# SCK_DATA_BOARD_2_2.net
KiCad netlist of a schematic drawn in EAGLE
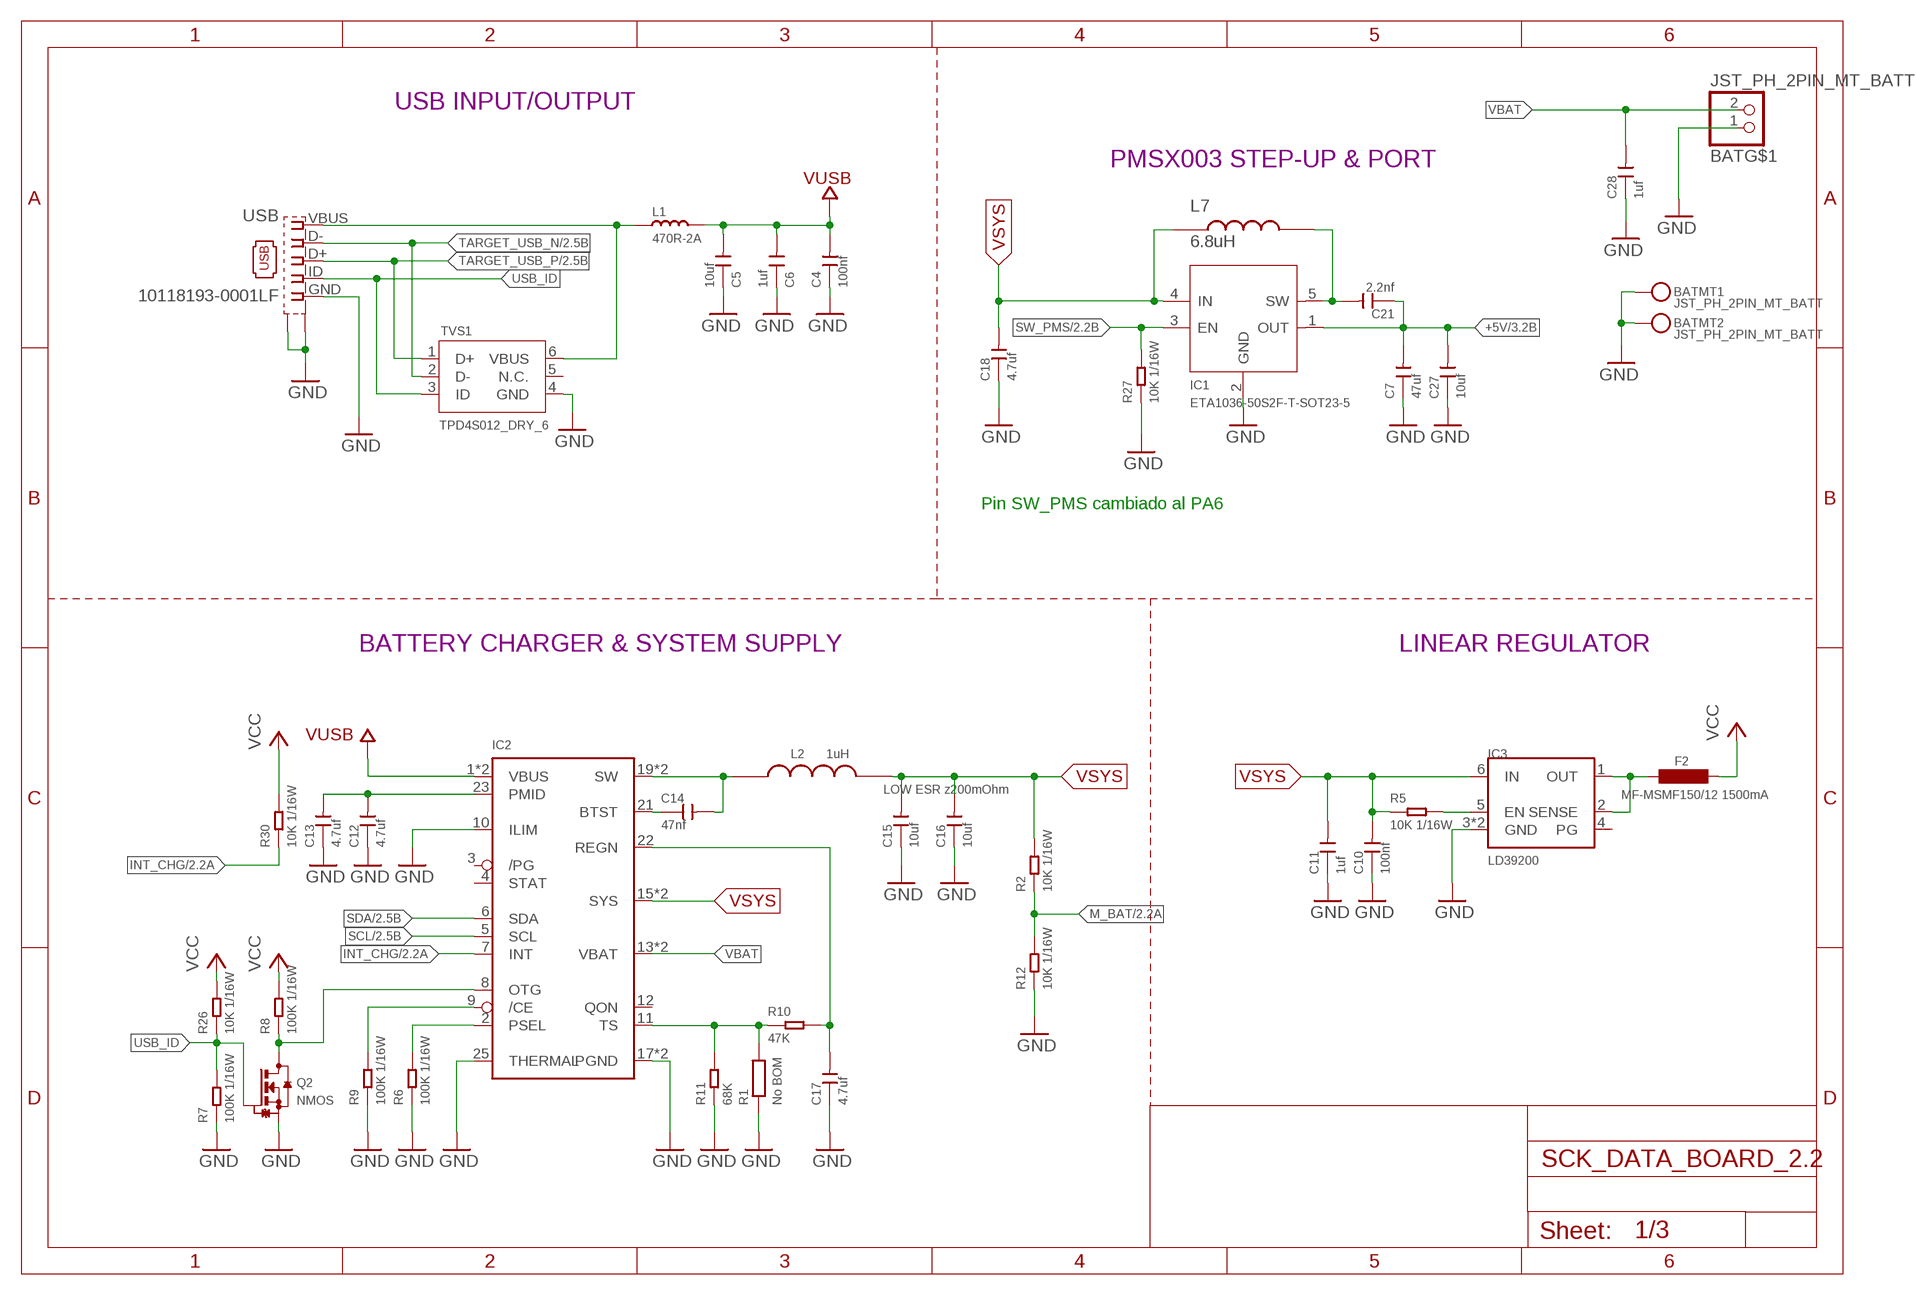
[diagram p0: schematic, sheet 1]
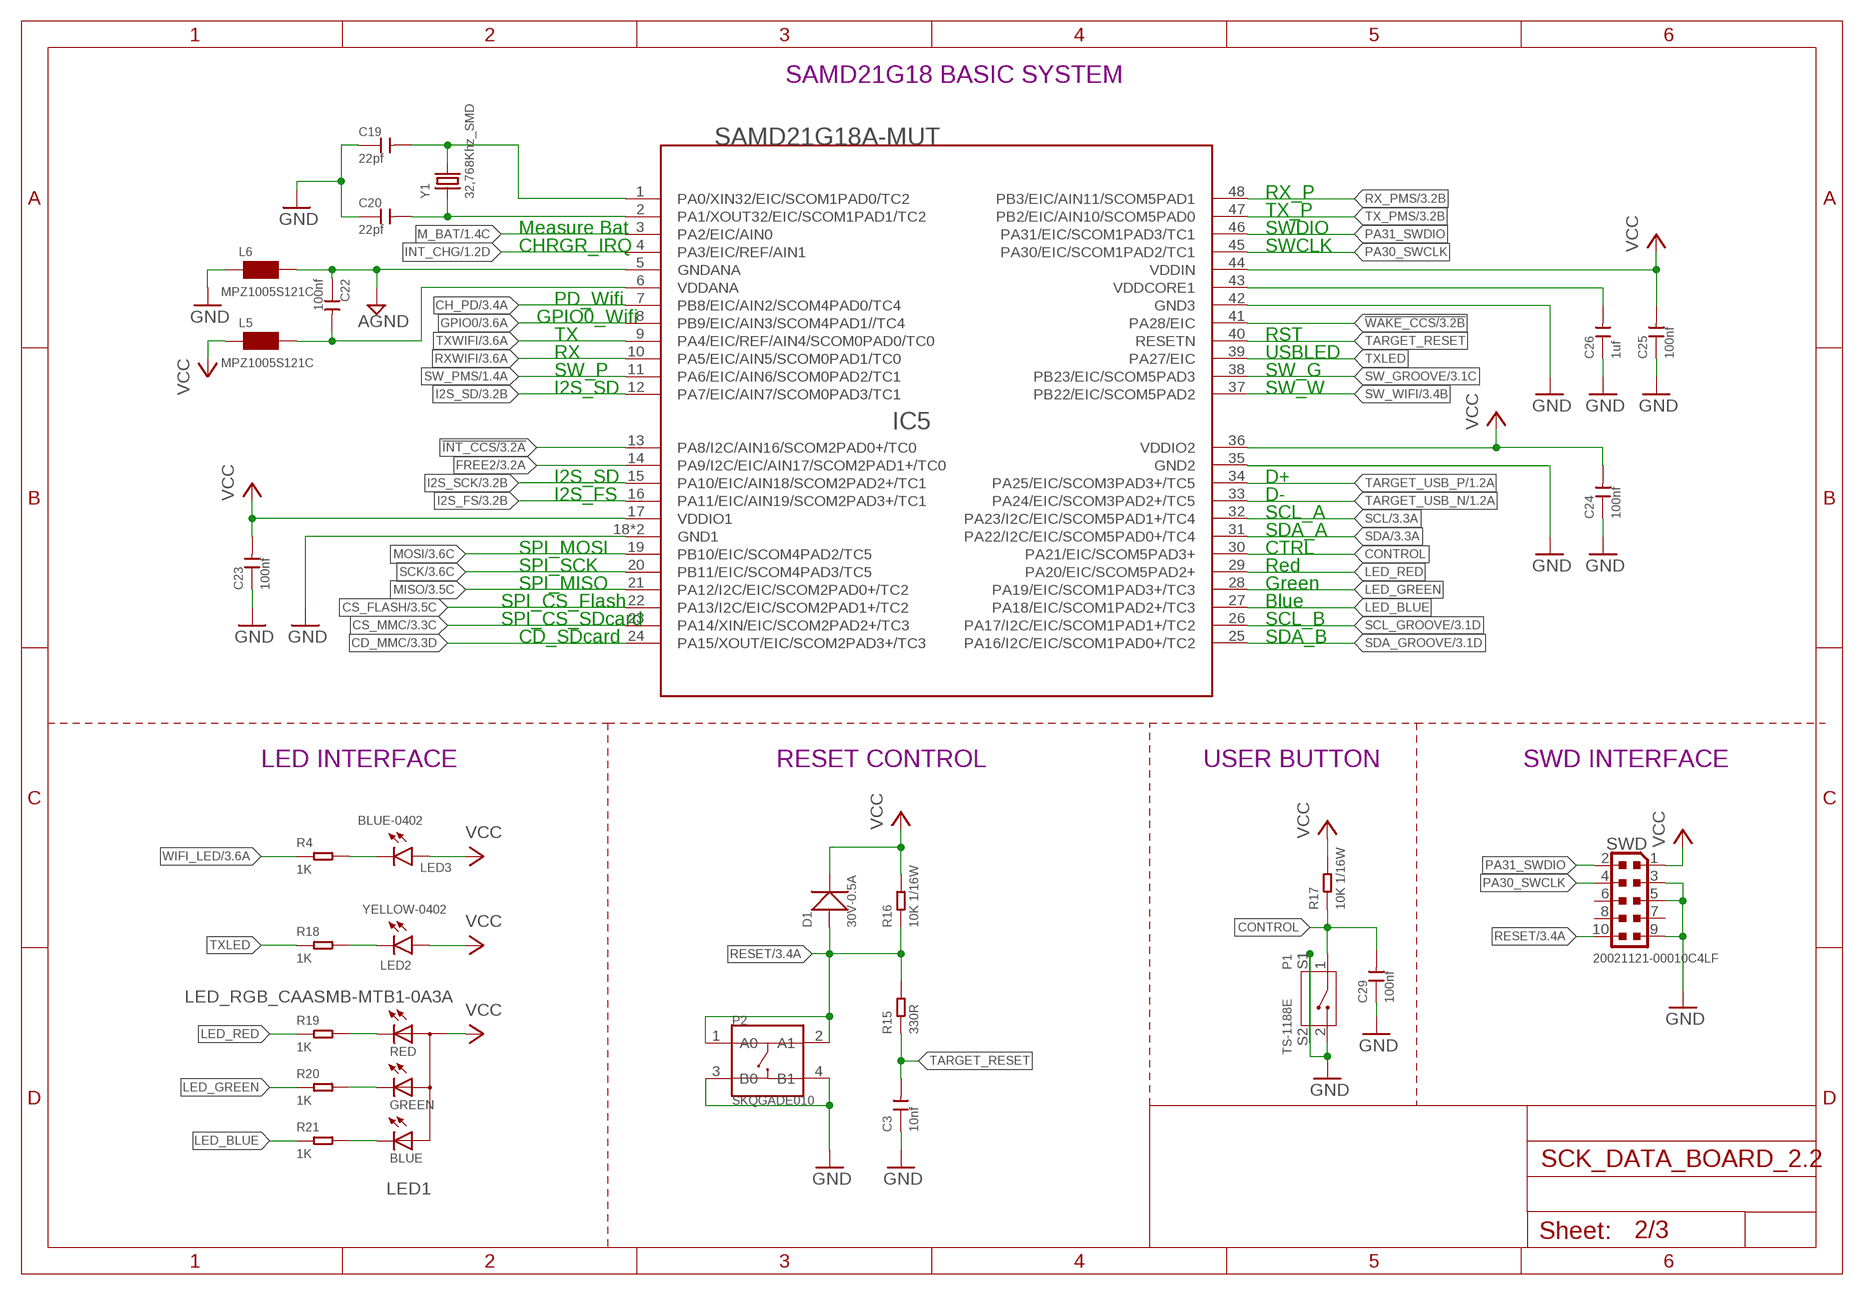
[diagram p1: schematic, sheet 2]
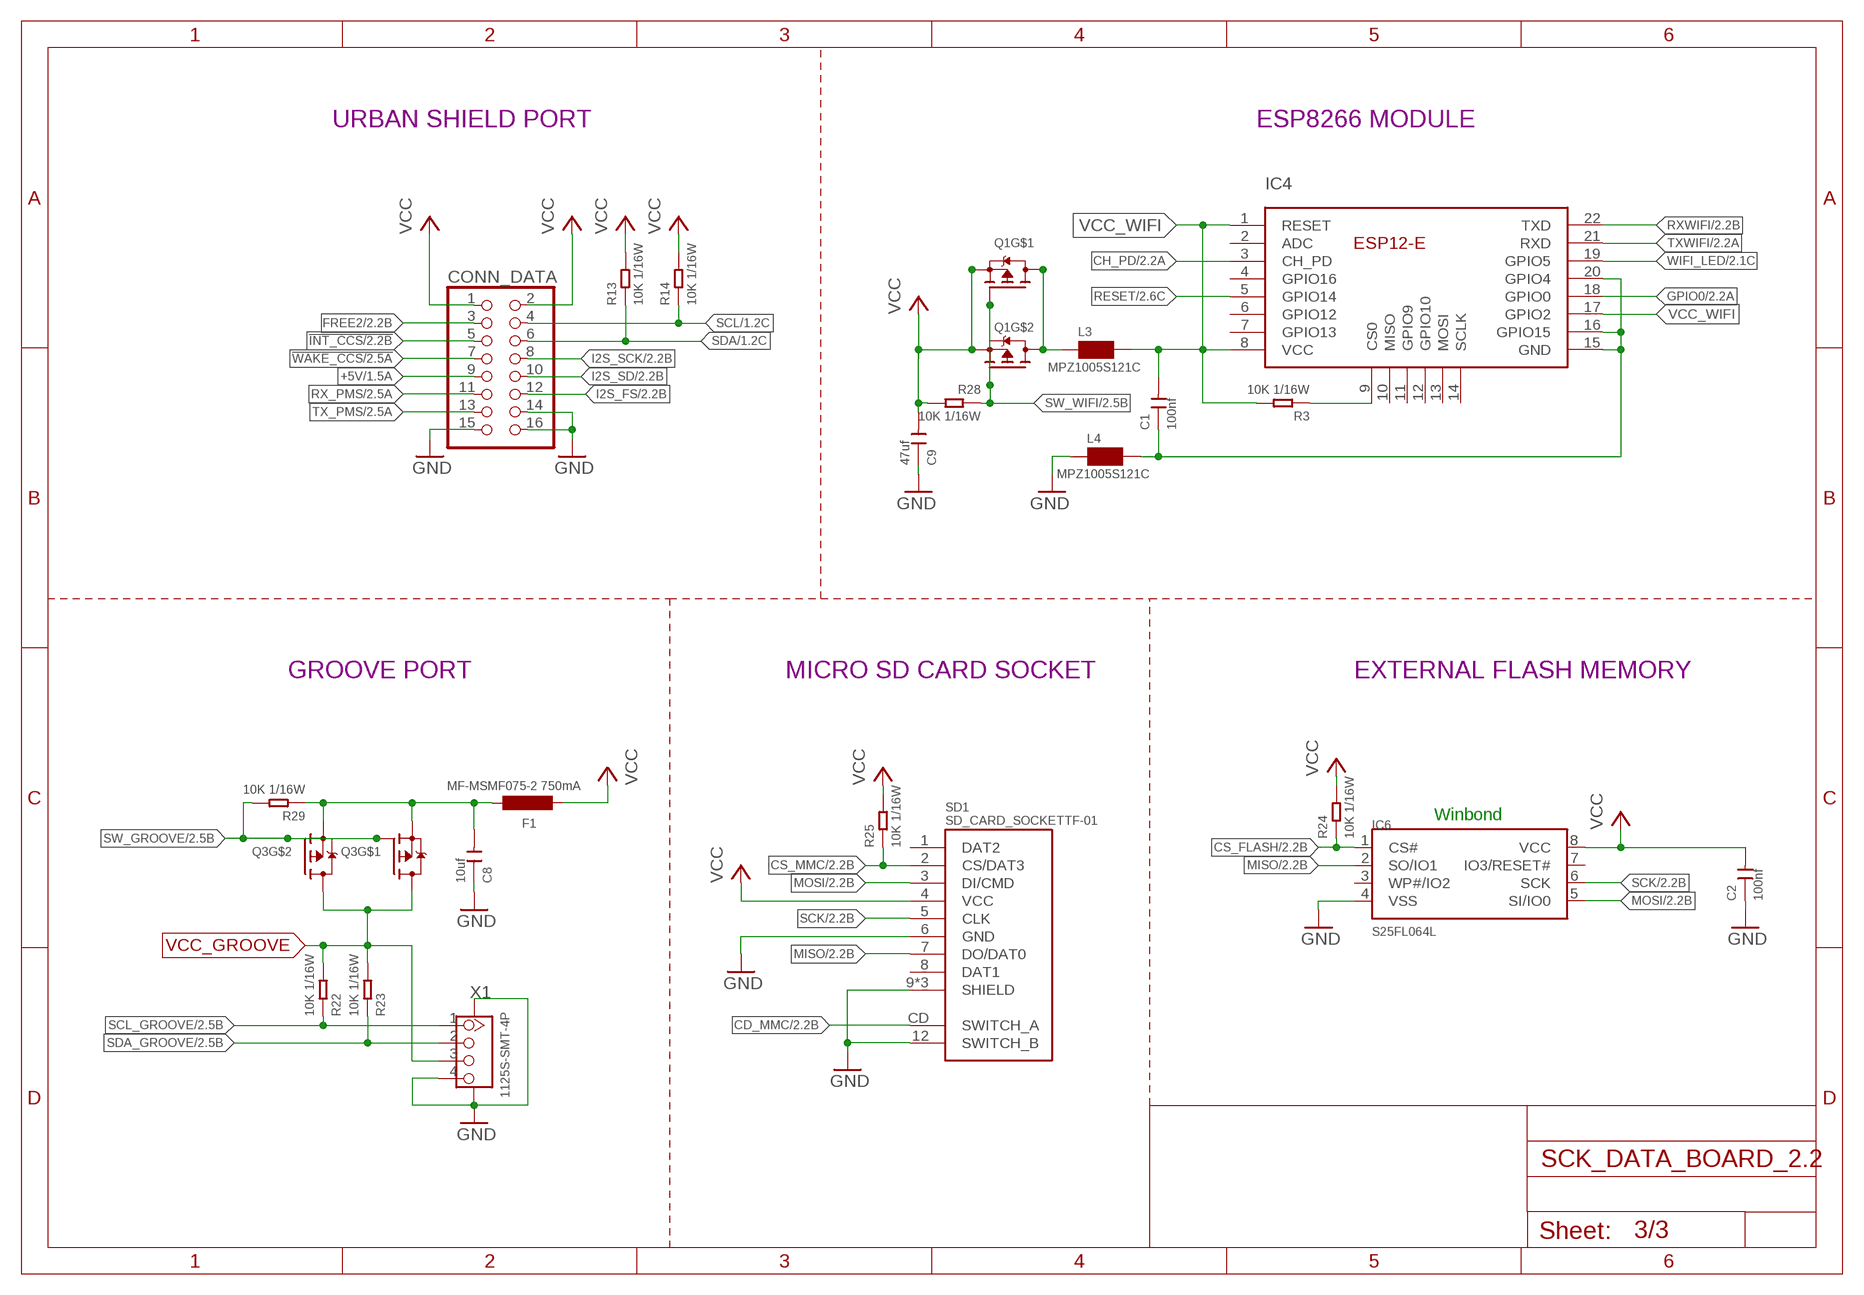
[diagram p2: schematic, sheet 3]

(export (version "E")
  (design (tool "Eeschema 10.0.6"))
  (components
    (comp (ref "C1")
      (value "100nf")
      (footprint "eagle-import:C0402")
      (fields (field (name "MPN") "CC0402KRX7R8BB104"))
      (libsource (lib "eagle-import") (part "CERAMIC-100NF-25V-10%-X7R(0402)"))
    )
    (comp (ref "C2")
      (value "100nf")
      (footprint "eagle-import:C0402")
      (fields (field (name "MPN") "CC0402KRX7R8BB104"))
      (libsource (lib "eagle-import") (part "CERAMIC-100NF-25V-10%-X7R(0402)"))
    )
    (comp (ref "C8")
      (value "10uf")
      (footprint "eagle-import:C1206")
      (fields (field (name "MPN") "CC1206KKX5R8BB106"))
      (libsource (lib "eagle-import") (part "CERAMIC-10UF-25V-10%-X5R(1206)"))
    )
    (comp (ref "C9")
      (value "47uf")
      (footprint "eagle-import:C1210")
      (fields (field (name "MPN") "GRM32ER71A476ME15L"))
      (libsource (lib "eagle-import") (part "CERAMIC-47UF-10V-20%-X7R(1210)"))
    )
    (comp (ref "CONN_DATA")
      (value "PINHD_2X8FEM_SMD")
      (footprint "eagle-import:PINHD_2X8_SMD_FEMALE_UNHOLED")
      (libsource (lib "eagle-import") (part "PINHD_2X8FEM_SMD"))
    )
    (comp (ref "F1")
      (value "MF-MSMF075-2 750mA")
      (footprint "eagle-import:L1812")
      (libsource (lib "eagle-import") (part "L-EUL1812"))
    )
    (comp (ref "IC4")
      (value "HANGAR_ESP-12-E")
      (footprint "eagle-import:HANGAR_ESP12-E")
      (libsource (lib "eagle-import") (part "HANGAR_ESP-12-E"))
    )
    (comp (ref "IC6")
      (value "S25FL064L")
      (footprint "eagle-import:SOIC_8-208MILS")
      (libsource (lib "eagle-import") (part "FLASH_S25FL064L"))
    )
    (comp (ref "L3")
      (value "MPZ1005S121C")
      (footprint "eagle-import:0402")
      (libsource (lib "eagle-import") (part "WE-CBF_0402"))
    )
    (comp (ref "L4")
      (value "MPZ1005S121C")
      (footprint "eagle-import:0402")
      (libsource (lib "eagle-import") (part "WE-CBF_0402"))
    )
    (comp (ref "Q1")
      (value "PMOS")
      (footprint "eagle-import:POWERPAK-SC70-6L")
      (fields (field (name "MPN") "SIA923AEDJ-T1-GE3 "))
      (libsource (lib "eagle-import") (part "MOSFET-PCHANNEL-DUAL"))
    )
    (comp (ref "Q3")
      (value "PMOS")
      (footprint "eagle-import:POWERPAK-SC70-6L")
      (libsource (lib "eagle-import") (part "MOSFET-PCHANNEL-DUAL"))
    )
    (comp (ref "R3")
      (value "10K 1/16W")
      (footprint "eagle-import:R0402")
      (fields (field (name "MPN") "RC0402FR-0710KL"))
      (libsource (lib "eagle-import") (part "SMD-RES-10K-1%-1/16W(0402)"))
    )
    (comp (ref "R13")
      (value "10K 1/16W")
      (footprint "eagle-import:R0402")
      (fields (field (name "MPN") "RC0402FR-0710KL"))
      (libsource (lib "eagle-import") (part "SMD-RES-10K-1%-1/16W(0402)"))
    )
    (comp (ref "R14")
      (value "10K 1/16W")
      (footprint "eagle-import:R0402")
      (fields (field (name "MPN") "RC0402FR-0710KL"))
      (libsource (lib "eagle-import") (part "SMD-RES-10K-1%-1/16W(0402)"))
    )
    (comp (ref "R22")
      (value "10K 1/16W")
      (footprint "eagle-import:R0402")
      (fields (field (name "MPN") "RC0402FR-0710KL"))
      (libsource (lib "eagle-import") (part "SMD-RES-10K-1%-1/16W(0402)"))
    )
    (comp (ref "R23")
      (value "10K 1/16W")
      (footprint "eagle-import:R0402")
      (fields (field (name "MPN") "RC0402FR-0710KL"))
      (libsource (lib "eagle-import") (part "SMD-RES-10K-1%-1/16W(0402)"))
    )
    (comp (ref "R24")
      (value "10K 1/16W")
      (footprint "eagle-import:R0402")
      (fields (field (name "MPN") "RC0402FR-0710KL"))
      (libsource (lib "eagle-import") (part "SMD-RES-10K-1%-1/16W(0402)"))
    )
    (comp (ref "R25")
      (value "10K 1/16W")
      (footprint "eagle-import:R0402")
      (fields (field (name "MPN") "RC0402FR-0710KL"))
      (libsource (lib "eagle-import") (part "SMD-RES-10K-1%-1/16W(0402)"))
    )
    (comp (ref "R28")
      (value "10K 1/16W")
      (footprint "eagle-import:R0402")
      (fields (field (name "MPN") "RC0402FR-0710KL"))
      (libsource (lib "eagle-import") (part "Seeed-Resistor_SMD-RES-10K-1%-1/16W(0402)"))
    )
    (comp (ref "R29")
      (value "10K 1/16W")
      (footprint "eagle-import:R0402")
      (fields (field (name "MPN") "RC0402FR-0710KL"))
      (libsource (lib "eagle-import") (part "Seeed-Resistor_SMD-RES-10K-1%-1/16W(0402)"))
    )
    (comp (ref "SD1")
      (value "SD_CARD_SOCKETTF-01")
      (footprint "eagle-import:TF-01")
      (fields (field (name "MPN") "320090008"))
      (libsource (lib "eagle-import") (part "SD_CARD_SOCKETTF-01"))
    )
    (comp (ref "X1")
      (value "1125S-SMT-4P")
      (footprint "eagle-import:CONNECTOR-NEW_HW4-SMD-2.0")
      (fields (field (name "MPN") "320110030"))
      (libsource (lib "eagle-import") (part "GROVE-CONNECTOR-SMDDD"))
    )
    (comp (ref "C3")
      (value "10nf")
      (footprint "eagle-import:C0402")
      (fields (field (name "MPN") "CC0402KRX7R9BB103"))
      (libsource (lib "eagle-import") (part "CERAMIC-10NF-50V-10%-X7R(0402)"))
    )
    (comp (ref "C19")
      (value "22pf")
      (footprint "eagle-import:C0402")
      (fields (field (name "MPN") "CC0402JRNPO9BN220"))
      (libsource (lib "eagle-import") (part "CERAMIC-22PF-50V-5%-NPO(0402)"))
    )
    (comp (ref "C20")
      (value "22pf")
      (footprint "eagle-import:C0402")
      (fields (field (name "MPN") "CC0402JRNPO9BN220"))
      (libsource (lib "eagle-import") (part "CERAMIC-22PF-50V-5%-NPO(0402)"))
    )
    (comp (ref "C22")
      (value "100nf")
      (footprint "eagle-import:C0402")
      (fields (field (name "MPN") "CC0402KRX7R8BB104"))
      (libsource (lib "eagle-import") (part "CERAMIC-100NF-25V-10%-X7R(0402)"))
    )
    (comp (ref "C23")
      (value "100nf")
      (footprint "eagle-import:C0402")
      (fields (field (name "MPN") "CC0402KRX7R8BB104"))
      (libsource (lib "eagle-import") (part "CERAMIC-100NF-25V-10%-X7R(0402)"))
    )
    (comp (ref "C24")
      (value "100nf")
      (footprint "eagle-import:C0402")
      (fields (field (name "MPN") "CC0402KRX7R8BB104"))
      (libsource (lib "eagle-import") (part "CERAMIC-100NF-25V-10%-X7R(0402)"))
    )
    (comp (ref "C25")
      (value "100nf")
      (footprint "eagle-import:C0402")
      (fields (field (name "MPN") "CC0402KRX7R8BB104"))
      (libsource (lib "eagle-import") (part "CERAMIC-100NF-25V-10%-X7R(0402)"))
    )
    (comp (ref "C26")
      (value "1uf")
      (footprint "eagle-import:C0805")
      (fields (field (name "MPN") "CC0805KKX7R8BB105"))
      (libsource (lib "eagle-import") (part "CERAMIC-1UF-25V-10%-X7R(0805)"))
    )
    (comp (ref "C29")
      (value "100nf")
      (footprint "eagle-import:C0402")
      (fields (field (name "MPN") "CC0402KRX7R8BB104"))
      (libsource (lib "eagle-import") (part "CERAMIC-100NF-25V-10%-X7R(0402)"))
    )
    (comp (ref "D1")
      (value "30V-0.5A")
      (footprint "eagle-import:SOD-323")
      (fields (field (name "MPN") "LRB551V-30T1G"))
      (libsource (lib "eagle-import") (part "SMD-DIODE-SCHOTTKY-30V-0.5A(SOD-323)"))
    )
    (comp (ref "IC5")
      (value "SAMD21G18A-MUT")
      (footprint "eagle-import:QFN48-7X7")
      (libsource (lib "eagle-import") (part "SAMD21G18A-MUT"))
    )
    (comp (ref "L5")
      (value "MPZ1005S121C")
      (footprint "eagle-import:0402")
      (libsource (lib "eagle-import") (part "WE-CBF_0402"))
    )
    (comp (ref "L6")
      (value "MPZ1005S121C")
      (footprint "eagle-import:0402")
      (libsource (lib "eagle-import") (part "WE-CBF_0402"))
    )
    (comp (ref "LED1")
      (value "LED_RGB_CAASMB-MTB1-0A3A")
      (footprint "eagle-import:HANGAR_P-LCC-4")
      (libsource (lib "eagle-import") (part "LED_RGB_CAASMB-MTB1-0A3A"))
    )
    (comp (ref "LED2")
      (value "YELLOW-0402")
      (footprint "eagle-import:CHIPLED_0402_YELLOW")
      (libsource (lib "eagle-import") (part "Hangar3D_37241589_LEDCHIPLED_0402_YELLOW"))
    )
    (comp (ref "LED3")
      (value "BLUE-0402")
      (footprint "eagle-import:CHIPLED_0402_BLUE")
      (libsource (lib "eagle-import") (part "LEDCHIPLED_0402_BLUE"))
    )
    (comp (ref "P1")
      (value "TS-1188E")
      (footprint "eagle-import:SW4-SMD-7.0X3.5X3.5MM-90D")
      (libsource (lib "eagle-import") (part "SMD-BUTTON(2+2P-7X3.5MM-90D)"))
    )
    (comp (ref "P2")
      (value "SKQGADE010")
      (footprint "eagle-import:SW4-SMD-5.2X5.2X1.5MM")
      (libsource (lib "eagle-import") (part "SMD-BUTTON(4P-5.2X5.2X1.5MM-SKQGADE010)-SKQGADE010"))
    )
    (comp (ref "R4")
      (value "1K")
      (footprint "eagle-import:R0402")
      (fields (field (name "MPN") "RC0402JR-071KL"))
      (libsource (lib "eagle-import") (part "SMD-RES-1K-5%-1/16W(0402)"))
    )
    (comp (ref "R15")
      (value "330R")
      (footprint "eagle-import:R0402")
      (fields (field (name "MPN") "RC0402FR-07330RL"))
      (libsource (lib "eagle-import") (part "SMD-RES-330R-1%-1/16W(0402)"))
    )
    (comp (ref "R16")
      (value "10K 1/16W")
      (footprint "eagle-import:R0402")
      (fields (field (name "MPN") "RC0402FR-0710KL"))
      (libsource (lib "eagle-import") (part "SMD-RES-10K-1%-1/16W(0402)"))
    )
    (comp (ref "R17")
      (value "10K 1/16W")
      (footprint "eagle-import:R0402")
      (fields (field (name "MPN") "RC0402FR-0710KL"))
      (libsource (lib "eagle-import") (part "SMD-RES-10K-1%-1/16W(0402)"))
    )
    (comp (ref "R18")
      (value "1K")
      (footprint "eagle-import:R0402")
      (fields (field (name "MPN") "RC0402JR-071KL"))
      (libsource (lib "eagle-import") (part "SMD-RES-1K-5%-1/16W(0402)"))
    )
    (comp (ref "R19")
      (value "1K")
      (footprint "eagle-import:R0402")
      (fields (field (name "MPN") "RC0402JR-071KL"))
      (libsource (lib "eagle-import") (part "SMD-RES-1K-5%-1/16W(0402)"))
    )
    (comp (ref "R20")
      (value "1K")
      (footprint "eagle-import:R0402")
      (fields (field (name "MPN") "RC0402JR-071KL"))
      (libsource (lib "eagle-import") (part "SMD-RES-1K-5%-1/16W(0402)"))
    )
    (comp (ref "R21")
      (value "1K")
      (footprint "eagle-import:R0402")
      (fields (field (name "MPN") "RC0402JR-071KL"))
      (libsource (lib "eagle-import") (part "SMD-RES-1K-5%-1/16W(0402)"))
    )
    (comp (ref "SWD")
      (value "20021121-00010C4LF")
      (footprint "eagle-import:2X05_SMD_1.27MM")
      (libsource (lib "eagle-import") (part "PINHEAD_PINHD-2X5SMD"))
    )
    (comp (ref "Y1")
      (value "32,768Khz_SMD")
      (footprint "eagle-import:CRISTALLI_RESONATOR_EPSON_FC_145")
      (fields (field (name "PART_NUMBER") "ABS07-32.768KHZ-T"))
      (libsource (lib "eagle-import") (part "CRISTALLI_0213_ABS07-32.768KHZ-T"))
    )
    (comp (ref "BAT")
      (value "JST_PH_2PIN_MT_BATT")
      (footprint "eagle-import:JSTPH2_BATT")
      (libsource (lib "eagle-import") (part "JST_PH_2PIN_MT_BATT"))
    )
    (comp (ref "C4")
      (value "100nf")
      (footprint "eagle-import:C0402")
      (fields (field (name "MPN") "CC0402KRX7R8BB104"))
      (libsource (lib "eagle-import") (part "CERAMIC-100NF-25V-10%-X7R(0402)"))
    )
    (comp (ref "C5")
      (value "10uf")
      (footprint "eagle-import:C1206")
      (fields (field (name "MPN") "CC1206KKX5R8BB106"))
      (libsource (lib "eagle-import") (part "CERAMIC-10UF-25V-10%-X5R(1206)"))
    )
    (comp (ref "C6")
      (value "1uf")
      (footprint "eagle-import:C0805")
      (fields (field (name "MPN") "CC0805KKX7R8BB105"))
      (libsource (lib "eagle-import") (part "CERAMIC-1UF-25V-10%-X7R(0805)"))
    )
    (comp (ref "C7")
      (value "47uf")
      (footprint "eagle-import:C0805")
      (fields (field (name "MPN") "CC0805MKX5R5BB476"))
      (libsource (lib "eagle-import") (part "CERAMIC-47UF-6.3V-20%-X5R(0805)"))
    )
    (comp (ref "C10")
      (value "100nf")
      (footprint "eagle-import:C0402")
      (fields (field (name "MPN") "CC0402KRX7R8BB104"))
      (libsource (lib "eagle-import") (part "CERAMIC-100NF-25V-10%-X7R(0402)"))
    )
    (comp (ref "C11")
      (value "1uf")
      (footprint "eagle-import:C0805")
      (fields (field (name "MPN") "CC0805KKX7R8BB105"))
      (libsource (lib "eagle-import") (part "CERAMIC-1UF-25V-10%-X7R(0805)"))
    )
    (comp (ref "C12")
      (value "4.7uf")
      (footprint "eagle-import:C0603")
      (fields (field (name "MPN") "CC0603KRX5R6BB475"))
      (libsource (lib "eagle-import") (part "CERAMIC-4.7UF-10V-10%-X5R(0603)"))
    )
    (comp (ref "C13")
      (value "4.7uf")
      (footprint "eagle-import:C0603")
      (fields (field (name "MPN") "CC0603KRX5R6BB475"))
      (libsource (lib "eagle-import") (part "CERAMIC-4.7UF-10V-10%-X5R(0603)"))
    )
    (comp (ref "C14")
      (value "47nf")
      (footprint "eagle-import:C0402")
      (fields (field (name "MPN") "CC0402KRX7R8BB473"))
      (libsource (lib "eagle-import") (part "CERAMIC-47NF-25V-10%-X7R(0402)"))
    )
    (comp (ref "C15")
      (value "10uf")
      (footprint "eagle-import:C0603")
      (fields (field (name "MPN") "CC0603KRX5R6BB106"))
      (libsource (lib "eagle-import") (part "Seeed-OPL-Capacitor_CERAMIC-10UF-10V-10%-X5R(0603)"))
    )
    (comp (ref "C16")
      (value "10uf")
      (footprint "eagle-import:C0603")
      (fields (field (name "MPN") "CC0603KRX5R6BB106"))
      (libsource (lib "eagle-import") (part "Seeed-OPL-Capacitor_CERAMIC-10UF-10V-10%-X5R(0603)"))
    )
    (comp (ref "C17")
      (value "4.7uf")
      (footprint "eagle-import:C0603")
      (fields (field (name "MPN") "CC0603KRX5R6BB475"))
      (libsource (lib "eagle-import") (part "CERAMIC-4.7UF-10V-10%-X5R(0603)"))
    )
    (comp (ref "C18")
      (value "4.7uf")
      (footprint "eagle-import:C0603")
      (fields (field (name "MPN") "CC0603KRX5R6BB475"))
      (libsource (lib "eagle-import") (part "CERAMIC-4.7UF-10V-10%-X5R(0603)"))
    )
    (comp (ref "C21")
      (value "2.2nf")
      (footprint "eagle-import:C0402")
      (fields (field (name "MPN") "CC0402KRX7R9BB222"))
      (libsource (lib "eagle-import") (part "CERAMIC-2.2NF-50V-10%-X7R(0402)"))
    )
    (comp (ref "C27")
      (value "10uf")
      (footprint "eagle-import:C0603")
      (fields (field (name "MPN") "CC0603KRX5R6BB106"))
      (libsource (lib "eagle-import") (part "CERAMIC-10UF-10V-10%-X5R(0603)"))
    )
    (comp (ref "C28")
      (value "1uf")
      (footprint "eagle-import:C0805")
      (fields (field (name "MPN") "CC0805KKX7R8BB105"))
      (libsource (lib "eagle-import") (part "CERAMIC-1UF-25V-10%-X7R(0805)"))
    )
    (comp (ref "F2")
      (value "MF-MSMF150/12 1500mA")
      (footprint "eagle-import:L1812")
      (libsource (lib "eagle-import") (part "L-EUL1812"))
    )
    (comp (ref "IC1")
      (value "ETA1036-50S2F-T-SOT23-5")
      (footprint "eagle-import:SOT-23-5")
      (fields (field (name "MPN") "ETA1036-50S2F-T"))
      (libsource (lib "eagle-import") (part "PMIC-ETA1036-50S2F-T(SOT23-5)"))
    )
    (comp (ref "IC2")
      (value "BQ24259_VQFN(24)")
      (footprint "eagle-import:24-PIN_VQFN_THPAD")
      (libsource (lib "eagle-import") (part "BQ24259_VQFN(24)"))
    )
    (comp (ref "IC3")
      (value "LD39200")
      (footprint "eagle-import:DFN6_3X3MM")
      (libsource (lib "eagle-import") (part "LD39200"))
    )
    (comp (ref "L1")
      (value "470R-2A")
      (footprint "eagle-import:L0805")
      (fields (field (name "MPN") "WLB2012-471T20"))
      (libsource (lib "eagle-import") (part "SMD-FERRITE-BEAD-470R-2A(0805)'0805'"))
    )
    (comp (ref "L2")
      (value "1uH")
      (footprint "eagle-import:HANGAR_C1210")
      (libsource (lib "eagle-import") (part "LQH32PN1R0NNCL"))
    )
    (comp (ref "L7")
      (value "6.8uH")
      (footprint "eagle-import:IND_BOURNS_SRN3015TA_3X3_SMD")
      (libsource (lib "eagle-import") (part "RCL_L_SMD_SRN3015TA-6R8M"))
    )
    (comp (ref "Q2")
      (value "NMOS")
      (footprint "eagle-import:NMOS_UMT3")
      (libsource (lib "eagle-import") (part "NMOS_RJU003N03FRAT106"))
    )
    (comp (ref "R1")
      (value "No BOM")
      (footprint "eagle-import:HANGAR_R0402")
      (libsource (lib "eagle-import") (part "HANGAR_R-EU_R0402"))
    )
    (comp (ref "R2")
      (value "10K 1/16W")
      (footprint "eagle-import:R0402")
      (fields (field (name "MPN") "RC0402FR-0710KL"))
      (libsource (lib "eagle-import") (part "SMD-RES-10K-1%-1/16W(0402)"))
    )
    (comp (ref "R5")
      (value "10K 1/16W")
      (footprint "eagle-import:R0402")
      (fields (field (name "MPN") "RC0402FR-0710KL"))
      (libsource (lib "eagle-import") (part "SMD-RES-10K-1%-1/16W(0402)"))
    )
    (comp (ref "R6")
      (value "100K 1/16W")
      (footprint "eagle-import:R0402")
      (fields (field (name "MPN") "RC0402JR-07100KL"))
      (libsource (lib "eagle-import") (part "SMD-RES-100K-5%-1/16W(0402)"))
    )
    (comp (ref "R7")
      (value "100K 1/16W")
      (footprint "eagle-import:R0402")
      (fields (field (name "MPN") "RC0402JR-07100KL"))
      (libsource (lib "eagle-import") (part "SMD-RES-100K-5%-1/16W(0402)"))
    )
    (comp (ref "R8")
      (value "100K 1/16W")
      (footprint "eagle-import:R0402")
      (fields (field (name "MPN") "RC0402JR-07100KL"))
      (libsource (lib "eagle-import") (part "SMD-RES-100K-5%-1/16W(0402)"))
    )
    (comp (ref "R9")
      (value "100K 1/16W")
      (footprint "eagle-import:R0402")
      (fields (field (name "MPN") "RC0402JR-07100KL"))
      (libsource (lib "eagle-import") (part "SMD-RES-100K-5%-1/16W(0402)"))
    )
    (comp (ref "R10")
      (value "47K")
      (footprint "eagle-import:R0402")
      (fields (field (name "MPN") "RC0402JR-0747KL"))
      (libsource (lib "eagle-import") (part "SMD-RES-47K-5%-1/16W(0402)"))
    )
    (comp (ref "R11")
      (value "68K")
      (footprint "eagle-import:R0402")
      (fields (field (name "MPN") "RC0402JR-0768KL"))
      (libsource (lib "eagle-import") (part "SMD-RES-68K-50V-5%(0402)"))
    )
    (comp (ref "R12")
      (value "10K 1/16W")
      (footprint "eagle-import:R0402")
      (fields (field (name "MPN") "RC0402FR-0710KL"))
      (libsource (lib "eagle-import") (part "SMD-RES-10K-1%-1/16W(0402)"))
    )
    (comp (ref "R26")
      (value "10K 1/16W")
      (footprint "eagle-import:R0402")
      (fields (field (name "MPN") "RC0402FR-0710KL"))
      (libsource (lib "eagle-import") (part "SMD-RES-10K-1%-1/16W(0402)"))
    )
    (comp (ref "R27")
      (value "10K 1/16W")
      (footprint "eagle-import:R0402")
      (fields (field (name "MPN") "RC0402FR-0710KL"))
      (libsource (lib "eagle-import") (part "Seeed-Resistor_SMD-RES-10K-1%-1/16W(0402)"))
    )
    (comp (ref "R30")
      (value "10K 1/16W")
      (footprint "eagle-import:R0402")
      (fields (field (name "MPN") "RC0402FR-0710KL"))
      (libsource (lib "eagle-import") (part "SMD-RES-10K-1%-1/16W(0402)"))
    )
    (comp (ref "TVS1")
      (value "TPD4S012_DRY_6")
      (footprint "eagle-import:DRY6")
      (libsource (lib "eagle-import") (part "TPD4S012_DRY_6"))
    )
    (comp (ref "USB")
      (value "10118193-0001LF")
      (footprint "eagle-import:CON2_USB_MICRO_B_AT")
      (libsource (lib "eagle-import") (part "USB_MICRO_USB"))
    )
  )
  (nets
    (net (code "1") (name "+5V") (class "Default")
      (node (ref "C21") (pin "1") (pinfunction "1_1") (pintype "passive"))
      (node (ref "C27") (pin "2") (pinfunction "2_2") (pintype "passive"))
      (node (ref "C7") (pin "2") (pinfunction "2_2") (pintype "passive"))
      (node (ref "CONN_DATA") (pin "9") (pinfunction "9_9") (pintype "passive"))
      (node (ref "IC1") (pin "1") (pinfunction "OUT_1") (pintype "bidirectional"))
    )
    (net (code "2") (name "AGND") (class "Default")
      (node (ref "C22") (pin "1") (pinfunction "1_1") (pintype "passive"))
      (node (ref "IC5") (pin "5") (pinfunction "GNDANA_5") (pintype "power_in"))
      (node (ref "L6") (pin "2") (pinfunction "2_2") (pintype "passive"))
    )
    (net (code "3") (name "CD_MMC") (class "Default")
      (node (ref "IC5") (pin "24") (pinfunction "PA15/XOUT/EIC/SCOM2PAD3+/TC3_24") (pintype "bidirectional"))
      (node (ref "SD1") (pin "CD") (pinfunction "SWITCH_A_CD") (pintype "bidirectional"))
    )
    (net (code "4") (name "CH_PD") (class "Default")
      (node (ref "IC4") (pin "3") (pinfunction "CH_PD_3") (pintype "input"))
      (node (ref "IC5") (pin "7") (pinfunction "PB8/EIC/AIN2/SCOM4PAD0/TC4_7") (pintype "bidirectional"))
    )
    (net (code "5") (name "CONTROL") (class "Default")
      (node (ref "C29") (pin "2") (pinfunction "2_2") (pintype "passive"))
      (node (ref "IC5") (pin "30") (pinfunction "PA21/EIC/SCOM5PAD3+_30") (pintype "bidirectional"))
      (node (ref "P1") (pin "1") (pinfunction "1_1") (pintype "bidirectional"))
      (node (ref "R17") (pin "1") (pinfunction "1_1") (pintype "passive"))
    )
    (net (code "6") (name "CS_FLASH") (class "Default")
      (node (ref "IC5") (pin "22") (pinfunction "PA13/I2C/EIC/SCOM2PAD1+/TC2_22") (pintype "bidirectional"))
      (node (ref "IC6") (pin "1") (pinfunction "CS#_1") (pintype "bidirectional"))
      (node (ref "R24") (pin "1") (pinfunction "1_1") (pintype "passive"))
    )
    (net (code "7") (name "CS_MMC") (class "Default")
      (node (ref "IC5") (pin "23") (pinfunction "PA14/XIN/EIC/SCOM2PAD2+/TC3_23") (pintype "bidirectional"))
      (node (ref "R25") (pin "1") (pinfunction "1_1") (pintype "passive"))
      (node (ref "SD1") (pin "2") (pinfunction "CS/DAT3_2") (pintype "bidirectional"))
    )
    (net (code "8") (name "FREE2") (class "Default")
      (node (ref "CONN_DATA") (pin "3") (pinfunction "3_3") (pintype "passive"))
      (node (ref "IC5") (pin "14") (pinfunction "PA9/I2C/EIC/AIN17/SCOM2PAD1+/TC0_14") (pintype "bidirectional"))
    )
    (net (code "9") (name "GND") (class "Default")
      (node (ref "BAT") (pin "1") (pinfunction "1_1") (pintype "passive"))
      (node (ref "BAT") (pin "NC1") (pinfunction "P$1_NC1") (pintype "bidirectional"))
      (node (ref "BAT") (pin "NC2") (pinfunction "P$1_NC2") (pintype "bidirectional"))
      (node (ref "C10") (pin "1") (pinfunction "1_1") (pintype "passive"))
      (node (ref "C11") (pin "1") (pinfunction "1_1") (pintype "passive"))
      (node (ref "C12") (pin "1") (pinfunction "1_1") (pintype "passive"))
      (node (ref "C13") (pin "1") (pinfunction "1_1") (pintype "passive"))
      (node (ref "C15") (pin "1") (pinfunction "1_1") (pintype "passive"))
      (node (ref "C16") (pin "1") (pinfunction "1_1") (pintype "passive"))
      (node (ref "C17") (pin "1") (pinfunction "1_1") (pintype "passive"))
      (node (ref "C18") (pin "1") (pinfunction "1_1") (pintype "passive"))
      (node (ref "C19") (pin "1") (pinfunction "1_1") (pintype "passive"))
      (node (ref "C2") (pin "1") (pinfunction "1_1") (pintype "passive"))
      (node (ref "C20") (pin "1") (pinfunction "1_1") (pintype "passive"))
      (node (ref "C23") (pin "1") (pinfunction "1_1") (pintype "passive"))
      (node (ref "C24") (pin "1") (pinfunction "1_1") (pintype "passive"))
      (node (ref "C25") (pin "1") (pinfunction "1_1") (pintype "passive"))
      (node (ref "C26") (pin "1") (pinfunction "1_1") (pintype "passive"))
      (node (ref "C27") (pin "1") (pinfunction "1_1") (pintype "passive"))
      (node (ref "C28") (pin "1") (pinfunction "1_1") (pintype "passive"))
      (node (ref "C29") (pin "1") (pinfunction "1_1") (pintype "passive"))
      (node (ref "C3") (pin "1") (pinfunction "1_1") (pintype "passive"))
      (node (ref "C4") (pin "1") (pinfunction "1_1") (pintype "passive"))
      (node (ref "C5") (pin "1") (pinfunction "1_1") (pintype "passive"))
      (node (ref "C6") (pin "1") (pinfunction "1_1") (pintype "passive"))
      (node (ref "C7") (pin "1") (pinfunction "1_1") (pintype "passive"))
      (node (ref "C8") (pin "1") (pinfunction "1_1") (pintype "passive"))
      (node (ref "C9") (pin "1") (pinfunction "1_1") (pintype "passive"))
      (node (ref "CONN_DATA") (pin "14") (pinfunction "14_14") (pintype "passive"))
      (node (ref "CONN_DATA") (pin "15") (pinfunction "15_15") (pintype "passive"))
      (node (ref "CONN_DATA") (pin "16") (pinfunction "16_16") (pintype "passive"))
      (node (ref "IC1") (pin "2") (pinfunction "GND_2") (pintype "bidirectional"))
      (node (ref "IC2") (pin "10") (pinfunction "ILIM_10") (pintype "bidirectional"))
      (node (ref "IC2") (pin "17") (pinfunction "PGND_17") (pintype "bidirectional"))
      (node (ref "IC2") (pin "18") (pinfunction "PGND_18") (pintype "bidirectional"))
      (node (ref "IC2") (pin "25") (pinfunction "THERMAL_25") (pintype "bidirectional"))
      (node (ref "IC3") (pin "3") (pinfunction "GND_3") (pintype "bidirectional"))
      (node (ref "IC3") (pin "7") (pinfunction "GND_7") (pintype "bidirectional"))
      (node (ref "IC5") (pin "18") (pinfunction "GND1_18") (pintype "power_in"))
      (node (ref "IC5") (pin "35") (pinfunction "GND2_35") (pintype "power_in"))
      (node (ref "IC5") (pin "42") (pinfunction "GND3_42") (pintype "power_in"))
      (node (ref "IC5") (pin "TP") (pinfunction "GND1_TP") (pintype "power_in"))
      (node (ref "IC6") (pin "4") (pinfunction "VSS_4") (pintype "bidirectional"))
      (node (ref "L4") (pin "2") (pinfunction "2_2") (pintype "passive"))
      (node (ref "L6") (pin "1") (pinfunction "1_1") (pintype "passive"))
      (node (ref "P1") (pin "2") (pinfunction "2_2") (pintype "bidirectional"))
      (node (ref "P1") (pin "S1") (pinfunction "S1_S1") (pintype "bidirectional"))
      (node (ref "P1") (pin "S2") (pinfunction "S2_S2") (pintype "bidirectional"))
      (node (ref "P2") (pin "3") (pinfunction "B0_3") (pintype "bidirectional"))
      (node (ref "P2") (pin "4") (pinfunction "B1_4") (pintype "bidirectional"))
      (node (ref "Q2") (pin "1") (pinfunction "S_1") (pintype "passive"))
      (node (ref "R1") (pin "1") (pinfunction "1_1") (pintype "passive"))
      (node (ref "R11") (pin "1") (pinfunction "1_1") (pintype "passive"))
      (node (ref "R12") (pin "1") (pinfunction "1_1") (pintype "passive"))
      (node (ref "R27") (pin "1") (pinfunction "1_1") (pintype "passive"))
      (node (ref "R6") (pin "1") (pinfunction "1_1") (pintype "passive"))
      (node (ref "R7") (pin "1") (pinfunction "1_1") (pintype "passive"))
      (node (ref "R9") (pin "1") (pinfunction "1_1") (pintype "passive"))
      (node (ref "SD1") (pin "10") (pinfunction "SHIELD_10") (pintype "bidirectional"))
      (node (ref "SD1") (pin "11") (pinfunction "SHIELD_11") (pintype "bidirectional"))
      (node (ref "SD1") (pin "12") (pinfunction "SWITCH_B_12") (pintype "bidirectional"))
      (node (ref "SD1") (pin "6") (pinfunction "GND_6") (pintype "bidirectional"))
      (node (ref "SD1") (pin "9") (pinfunction "SHIELD_9") (pintype "bidirectional"))
      (node (ref "SWD") (pin "3") (pinfunction "3_3") (pintype "passive"))
      (node (ref "SWD") (pin "5") (pinfunction "5_5") (pintype "passive"))
      (node (ref "SWD") (pin "9") (pinfunction "9_9") (pintype "passive"))
      (node (ref "TVS1") (pin "4") (pinfunction "GND_4") (pintype "passive"))
      (node (ref "USB") (pin "GND") (pinfunction "5_GND") (pintype "passive"))
      (node (ref "USB") (pin "P$1") (pinfunction "S1_P$1") (pintype "passive"))
      (node (ref "USB") (pin "P$2") (pinfunction "S1_P$2") (pintype "passive"))
      (node (ref "USB") (pin "P$3") (pinfunction "S1_P$3") (pintype "passive"))
      (node (ref "USB") (pin "P$4") (pinfunction "S1_P$4") (pintype "passive"))
      (node (ref "USB") (pin "P$5") (pinfunction "S1_P$5") (pintype "passive"))
      (node (ref "USB") (pin "P$6") (pinfunction "S1_P$6") (pintype "passive"))
      (node (ref "USB") (pin "P$7") (pinfunction "S1_P$7") (pintype "passive"))
      (node (ref "USB") (pin "P$8") (pinfunction "S1_P$8") (pintype "passive"))
      (node (ref "USB") (pin "S1") (pinfunction "S2_S1") (pintype "passive"))
      (node (ref "USB") (pin "S2") (pinfunction "S2_S2") (pintype "passive"))
      (node (ref "USB") (pin "S3") (pinfunction "S2_S3") (pintype "passive"))
      (node (ref "USB") (pin "S4") (pinfunction "S2_S4") (pintype "passive"))
      (node (ref "USB") (pin "S5") (pinfunction "S2_S5") (pintype "passive"))
      (node (ref "USB") (pin "S6") (pinfunction "S2_S6") (pintype "passive"))
      (node (ref "X1") (pin "4") (pinfunction "4_4") (pintype "bidirectional"))
      (node (ref "X1") (pin "SS1") (pinfunction "SS1_SS1") (pintype "bidirectional"))
      (node (ref "X1") (pin "SS2") (pinfunction "SS2_SS2") (pintype "bidirectional"))
    )
    (net (code "10") (name "GPIO0") (class "Default")
      (node (ref "IC4") (pin "18") (pinfunction "GPIO0_18") (pintype "bidirectional"))
      (node (ref "IC5") (pin "8") (pinfunction "PB9/EIC/AIN3/SCOM4PAD1//TC4_8") (pintype "bidirectional"))
    )
    (net (code "11") (name "I2S_FS") (class "Default")
      (node (ref "CONN_DATA") (pin "12") (pinfunction "12_12") (pintype "passive"))
      (node (ref "IC5") (pin "16") (pinfunction "PA11/EIC/AIN19/SCOM2PAD3+/TC1_16") (pintype "bidirectional"))
    )
    (net (code "12") (name "I2S_SCK") (class "Default")
      (node (ref "CONN_DATA") (pin "8") (pinfunction "8_8") (pintype "passive"))
      (node (ref "IC5") (pin "15") (pinfunction "PA10/EIC/AIN18/SCOM2PAD2+/TC1_15") (pintype "bidirectional"))
    )
    (net (code "13") (name "I2S_SD") (class "Default")
      (node (ref "CONN_DATA") (pin "10") (pinfunction "10_10") (pintype "passive"))
      (node (ref "IC5") (pin "12") (pinfunction "PA7/EIC/AIN7/SCOM0PAD3/TC1_12") (pintype "bidirectional"))
    )
    (net (code "14") (name "INT_CHG") (class "Default")
      (node (ref "IC2") (pin "7") (pinfunction "INT_7") (pintype "bidirectional"))
      (node (ref "IC5") (pin "4") (pinfunction "PA3/EIC/REF/AIN1_4") (pintype "bidirectional"))
      (node (ref "R30") (pin "1") (pinfunction "1_1") (pintype "passive"))
    )
    (net (code "15") (name "LED_BLUE") (class "Default")
      (node (ref "IC5") (pin "27") (pinfunction "PA18/EIC/SCOM1PAD2+/TC3_27") (pintype "bidirectional"))
      (node (ref "R21") (pin "1") (pinfunction "1_1") (pintype "passive"))
    )
    (net (code "16") (name "LED_GREEN") (class "Default")
      (node (ref "IC5") (pin "28") (pinfunction "PA19/EIC/SCOM1PAD3+/TC3_28") (pintype "bidirectional"))
      (node (ref "R20") (pin "1") (pinfunction "1_1") (pintype "passive"))
    )
    (net (code "17") (name "LED_RED") (class "Default")
      (node (ref "IC5") (pin "29") (pinfunction "PA20/EIC/SCOM5PAD2+_29") (pintype "bidirectional"))
      (node (ref "R19") (pin "1") (pinfunction "1_1") (pintype "passive"))
    )
    (net (code "18") (name "MISO") (class "Default")
      (node (ref "IC5") (pin "21") (pinfunction "PA12/I2C/EIC/SCOM2PAD0+/TC2_21") (pintype "bidirectional"))
      (node (ref "IC6") (pin "2") (pinfunction "SO/IO1_2") (pintype "bidirectional"))
      (node (ref "SD1") (pin "7") (pinfunction "DO/DAT0_7") (pintype "bidirectional"))
    )
    (net (code "19") (name "MOSI") (class "Default")
      (node (ref "IC5") (pin "19") (pinfunction "PB10/EIC/SCOM4PAD2/TC5_19") (pintype "bidirectional"))
      (node (ref "IC6") (pin "5") (pinfunction "SI/IO0_5") (pintype "bidirectional"))
      (node (ref "SD1") (pin "3") (pinfunction "DI/CMD_3") (pintype "bidirectional"))
    )
    (net (code "20") (name "M_BAT") (class "Default")
      (node (ref "IC5") (pin "3") (pinfunction "PA2/EIC/AIN0_3") (pintype "bidirectional"))
      (node (ref "R12") (pin "2") (pinfunction "2_2") (pintype "passive"))
      (node (ref "R2") (pin "1") (pinfunction "1_1") (pintype "passive"))
    )
    (net (code "21") (name "Net-(C14-Pad2)") (class "Default")
      (node (ref "C14") (pin "2") (pinfunction "2_2") (pintype "passive"))
      (node (ref "IC2") (pin "19") (pinfunction "SW_19") (pintype "bidirectional"))
      (node (ref "IC2") (pin "20") (pinfunction "SW_20") (pintype "bidirectional"))
      (node (ref "L2") (pin "1") (pinfunction "1_1") (pintype "bidirectional"))
    )
    (net (code "22") (name "Net-(IC1-SW)") (class "Default")
      (node (ref "C21") (pin "2") (pinfunction "2_2") (pintype "passive"))
      (node (ref "IC1") (pin "5") (pinfunction "SW_5") (pintype "bidirectional"))
      (node (ref "L7") (pin "P$2") (pinfunction "P$2_P$2") (pintype "bidirectional"))
    )
    (net (code "23") (name "Net-(IC2-BTST)") (class "Default")
      (node (ref "C14") (pin "1") (pinfunction "1_1") (pintype "passive"))
      (node (ref "IC2") (pin "21") (pinfunction "BTST_21") (pintype "bidirectional"))
    )
    (net (code "24") (name "Net-(IC2-OTG)") (class "Default")
      (node (ref "IC2") (pin "8") (pinfunction "OTG_8") (pintype "bidirectional"))
      (node (ref "Q2") (pin "3") (pinfunction "D_3") (pintype "passive"))
      (node (ref "R8") (pin "1") (pinfunction "1_1") (pintype "passive"))
    )
    (net (code "25") (name "Net-(IC2-PMID)") (class "Default")
      (node (ref "C12") (pin "2") (pinfunction "2_2") (pintype "passive"))
      (node (ref "C13") (pin "2") (pinfunction "2_2") (pintype "passive"))
      (node (ref "IC2") (pin "23") (pinfunction "PMID_23") (pintype "bidirectional"))
    )
    (net (code "26") (name "Net-(IC2-PSEL)") (class "Default")
      (node (ref "IC2") (pin "2") (pinfunction "PSEL_2") (pintype "bidirectional"))
      (node (ref "R6") (pin "2") (pinfunction "2_2") (pintype "passive"))
    )
    (net (code "27") (name "Net-(IC2-REGN)") (class "Default")
      (node (ref "C17") (pin "2") (pinfunction "2_2") (pintype "passive"))
      (node (ref "IC2") (pin "22") (pinfunction "REGN_22") (pintype "bidirectional"))
      (node (ref "R10") (pin "2") (pinfunction "2_2") (pintype "passive"))
    )
    (net (code "28") (name "Net-(IC2-TS)") (class "Default")
      (node (ref "IC2") (pin "11") (pinfunction "TS_11") (pintype "bidirectional"))
      (node (ref "R1") (pin "2") (pinfunction "2_2") (pintype "passive"))
      (node (ref "R10") (pin "1") (pinfunction "1_1") (pintype "passive"))
      (node (ref "R11") (pin "2") (pinfunction "2_2") (pintype "passive"))
    )
    (net (code "29") (name "Net-(IC2-{slash}CE)") (class "Default")
      (node (ref "IC2") (pin "9") (pinfunction "/CE_9") (pintype "bidirectional"))
      (node (ref "R9") (pin "2") (pinfunction "2_2") (pintype "passive"))
    )
    (net (code "30") (name "Net-(IC3-EN)") (class "Default")
      (node (ref "IC3") (pin "5") (pinfunction "EN_5") (pintype "bidirectional"))
      (node (ref "R5") (pin "2") (pinfunction "2_2") (pintype "passive"))
    )
    (net (code "31") (name "Net-(IC3-OUT)") (class "Default")
      (node (ref "F2") (pin "2") (pinfunction "2_2") (pintype "passive"))
      (node (ref "IC3") (pin "1") (pinfunction "OUT_1") (pintype "bidirectional"))
      (node (ref "IC3") (pin "2") (pinfunction "SENSE_2") (pintype "bidirectional"))
    )
    (net (code "32") (name "Net-(IC4-CS0)") (class "Default")
      (node (ref "IC4") (pin "9") (pinfunction "CS0_9") (pintype "input"))
      (node (ref "R3") (pin "1") (pinfunction "1_1") (pintype "passive"))
    )
    (net (code "33") (name "Net-(IC4-GND)") (class "Default")
      (node (ref "C1") (pin "1") (pinfunction "1_1") (pintype "passive"))
      (node (ref "IC4") (pin "15") (pinfunction "GND_15") (pintype "power_in"))
      (node (ref "IC4") (pin "16") (pinfunction "GPIO15_16") (pintype "bidirectional"))
      (node (ref "IC4") (pin "20") (pinfunction "GPIO4_20") (pintype "bidirectional"))
      (node (ref "L4") (pin "1") (pinfunction "1_1") (pintype "passive"))
    )
    (net (code "34") (name "Net-(IC5-PA0{slash}XIN32{slash}EIC{slash}SCOM1PAD0{slash}TC2)") (class "Default")
      (node (ref "C19") (pin "2") (pinfunction "2_2") (pintype "passive"))
      (node (ref "IC5") (pin "1") (pinfunction "PA0/XIN32/EIC/SCOM1PAD0/TC2_1") (pintype "bidirectional"))
      (node (ref "Y1") (pin "P$2") (pinfunction "2_P$2") (pintype "bidirectional"))
    )
    (net (code "35") (name "Net-(IC5-PA1{slash}XOUT32{slash}EIC{slash}SCOM1PAD1{slash}TC2)") (class "Default")
      (node (ref "C20") (pin "2") (pinfunction "2_2") (pintype "passive"))
      (node (ref "IC5") (pin "2") (pinfunction "PA1/XOUT32/EIC/SCOM1PAD1/TC2_2") (pintype "bidirectional"))
      (node (ref "Y1") (pin "P$1") (pinfunction "1_P$1") (pintype "bidirectional"))
    )
    (net (code "36") (name "Net-(IC5-VDDANA)") (class "Default")
      (node (ref "C22") (pin "2") (pinfunction "2_2") (pintype "passive"))
      (node (ref "IC5") (pin "6") (pinfunction "VDDANA_6") (pintype "power_in"))
      (node (ref "L5") (pin "2") (pinfunction "2_2") (pintype "passive"))
    )
    (net (code "37") (name "Net-(IC5-VDDCORE1)") (class "Default")
      (node (ref "C26") (pin "2") (pinfunction "2_2") (pintype "passive"))
      (node (ref "IC5") (pin "43") (pinfunction "VDDCORE1_43") (pintype "input"))
    )
    (net (code "38") (name "Net-(L3-Pad2)") (class "Default")
      (node (ref "L3") (pin "2") (pinfunction "2_2") (pintype "passive"))
      (node (ref "Q1") (pin "3") (pinfunction "D_3") (pintype "passive"))
      (node (ref "Q1") (pin "6") (pinfunction "D_6") (pintype "passive"))
      (node (ref "Q1") (pin "TP1") (pinfunction "D_TP1") (pintype "passive"))
      (node (ref "Q1") (pin "TP2") (pinfunction "D_TP2") (pintype "passive"))
    )
    (net (code "39") (name "Net-(LED1-BLUE)") (class "Default")
      (node (ref "LED1") (pin "3") (pinfunction "BLUE_3") (pintype "passive"))
      (node (ref "R21") (pin "2") (pinfunction "2_2") (pintype "passive"))
    )
    (net (code "40") (name "Net-(LED1-GREEN)") (class "Default")
      (node (ref "LED1") (pin "2") (pinfunction "GREEN_2") (pintype "passive"))
      (node (ref "R20") (pin "2") (pinfunction "2_2") (pintype "passive"))
    )
    (net (code "41") (name "Net-(LED1-RED)") (class "Default")
      (node (ref "LED1") (pin "1") (pinfunction "RED_1") (pintype "passive"))
      (node (ref "R19") (pin "2") (pinfunction "2_2") (pintype "passive"))
    )
    (net (code "42") (name "Net-(LED2-C)") (class "Default")
      (node (ref "LED2") (pin "K") (pinfunction "C_K") (pintype "passive"))
      (node (ref "R18") (pin "2") (pinfunction "2_2") (pintype "passive"))
    )
    (net (code "43") (name "Net-(LED3-C)") (class "Default")
      (node (ref "LED3") (pin "K") (pinfunction "C_K") (pintype "passive"))
      (node (ref "R4") (pin "2") (pinfunction "2_2") (pintype "passive"))
    )
    (net (code "44") (name "Net-(Q3A-S)") (class "Default")
      (node (ref "C8") (pin "2") (pinfunction "2_2") (pintype "passive"))
      (node (ref "F1") (pin "1") (pinfunction "1_1") (pintype "passive"))
      (node (ref "Q3") (pin "1") (pinfunction "S_1") (pintype "passive"))
      (node (ref "Q3") (pin "4") (pinfunction "S_4") (pintype "passive"))
      (node (ref "R29") (pin "1") (pinfunction "1_1") (pintype "passive"))
    )
    (net (code "45") (name "Net-(TVS1-VBUS)") (class "Default")
      (node (ref "L1") (pin "1") (pinfunction "1_1") (pintype "passive"))
      (node (ref "TVS1") (pin "6") (pinfunction "VBUS_6") (pintype "passive"))
      (node (ref "USB") (pin "VBUS") (pinfunction "1_VBUS") (pintype "passive"))
    )
    (net (code "46") (name "PA30_SWCLK") (class "Default")
      (node (ref "IC5") (pin "45") (pinfunction "PA30/EIC/SCOM1PAD2/TC1_45") (pintype "bidirectional"))
      (node (ref "SWD") (pin "4") (pinfunction "4_4") (pintype "passive"))
    )
    (net (code "47") (name "PA31_SWDIO") (class "Default")
      (node (ref "IC5") (pin "46") (pinfunction "PA31/EIC/SCOM1PAD3/TC1_46") (pintype "bidirectional"))
      (node (ref "SWD") (pin "2") (pinfunction "2_2") (pintype "passive"))
    )
    (net (code "48") (name "RESET") (class "Default")
      (node (ref "D1") (pin "+") (pinfunction "+_+") (pintype "passive"))
      (node (ref "IC4") (pin "5") (pinfunction "GPIO14_5") (pintype "bidirectional"))
      (node (ref "P2") (pin "1") (pinfunction "A0_1") (pintype "bidirectional"))
      (node (ref "P2") (pin "2") (pinfunction "A1_2") (pintype "bidirectional"))
      (node (ref "R15") (pin "2") (pinfunction "2_2") (pintype "passive"))
      (node (ref "R16") (pin "1") (pinfunction "1_1") (pintype "passive"))
      (node (ref "SWD") (pin "10") (pinfunction "10_10") (pintype "passive"))
    )
    (net (code "49") (name "RXWIFI") (class "Default")
      (node (ref "IC4") (pin "22") (pinfunction "TXD_22") (pintype "output"))
      (node (ref "IC5") (pin "10") (pinfunction "PA5/EIC/AIN5/SCOM0PAD1/TC0_10") (pintype "bidirectional"))
    )
    (net (code "50") (name "RX_PMS") (class "Default")
      (node (ref "CONN_DATA") (pin "11") (pinfunction "11_11") (pintype "passive"))
      (node (ref "IC5") (pin "48") (pinfunction "PB3/EIC/AIN11/SCOM5PAD1_48") (pintype "bidirectional"))
    )
    (net (code "51") (name "SCK") (class "Default")
      (node (ref "IC5") (pin "20") (pinfunction "PB11/EIC/SCOM4PAD3/TC5_20") (pintype "bidirectional"))
      (node (ref "IC6") (pin "6") (pinfunction "SCK_6") (pintype "bidirectional"))
      (node (ref "SD1") (pin "5") (pinfunction "CLK_5") (pintype "bidirectional"))
    )
    (net (code "52") (name "SCL") (class "Default")
      (node (ref "CONN_DATA") (pin "4") (pinfunction "4_4") (pintype "passive"))
      (node (ref "IC2") (pin "5") (pinfunction "SCL_5") (pintype "bidirectional"))
      (node (ref "IC5") (pin "32") (pinfunction "PA23/I2C/EIC/SCOM5PAD1+/TC4_32") (pintype "bidirectional"))
      (node (ref "R14") (pin "1") (pinfunction "1_1") (pintype "passive"))
    )
    (net (code "53") (name "SCL_GROOVE") (class "Default")
      (node (ref "IC5") (pin "26") (pinfunction "PA17/I2C/EIC/SCOM1PAD1+/TC2_26") (pintype "bidirectional"))
      (node (ref "R22") (pin "1") (pinfunction "1_1") (pintype "passive"))
      (node (ref "X1") (pin "1") (pinfunction "1_1") (pintype "bidirectional"))
    )
    (net (code "54") (name "SDA") (class "Default")
      (node (ref "CONN_DATA") (pin "6") (pinfunction "6_6") (pintype "passive"))
      (node (ref "IC2") (pin "6") (pinfunction "SDA_6") (pintype "bidirectional"))
      (node (ref "IC5") (pin "31") (pinfunction "PA22/I2C/EIC/SCOM5PAD0+/TC4_31") (pintype "bidirectional"))
      (node (ref "R13") (pin "1") (pinfunction "1_1") (pintype "passive"))
    )
    (net (code "55") (name "SDA_GROOVE") (class "Default")
      (node (ref "IC5") (pin "25") (pinfunction "PA16/I2C/EIC/SCOM1PAD0+/TC2_25") (pintype "bidirectional"))
      (node (ref "R23") (pin "1") (pinfunction "1_1") (pintype "passive"))
      (node (ref "X1") (pin "2") (pinfunction "2_2") (pintype "bidirectional"))
    )
    (net (code "56") (name "SW_GROOVE") (class "Default")
      (node (ref "IC5") (pin "38") (pinfunction "PB23/EIC/SCOM5PAD3_38") (pintype "bidirectional"))
      (node (ref "Q3") (pin "2") (pinfunction "G_2") (pintype "passive"))
      (node (ref "Q3") (pin "5") (pinfunction "G_5") (pintype "passive"))
      (node (ref "R29") (pin "2") (pinfunction "2_2") (pintype "passive"))
    )
    (net (code "57") (name "SW_PMS") (class "Default")
      (node (ref "IC1") (pin "3") (pinfunction "EN_3") (pintype "bidirectional"))
      (node (ref "IC5") (pin "11") (pinfunction "PA6/EIC/AIN6/SCOM0PAD2/TC1_11") (pintype "bidirectional"))
      (node (ref "R27") (pin "2") (pinfunction "2_2") (pintype "passive"))
    )
    (net (code "58") (name "SW_WIFI") (class "Default")
      (node (ref "IC5") (pin "37") (pinfunction "PB22/EIC/SCOM5PAD2_37") (pintype "bidirectional"))
      (node (ref "Q1") (pin "2") (pinfunction "G_2") (pintype "passive"))
      (node (ref "Q1") (pin "5") (pinfunction "G_5") (pintype "passive"))
      (node (ref "R28") (pin "1") (pinfunction "1_1") (pintype "passive"))
    )
    (net (code "59") (name "TARGET_RESET") (class "Default")
      (node (ref "C3") (pin "2") (pinfunction "2_2") (pintype "passive"))
      (node (ref "IC5") (pin "40") (pinfunction "RESETN_40") (pintype "bidirectional"))
      (node (ref "R15") (pin "1") (pinfunction "1_1") (pintype "passive"))
    )
    (net (code "60") (name "TARGET_USB_N") (class "Default")
      (node (ref "IC5") (pin "33") (pinfunction "PA24/EIC/SCOM3PAD2+/TC5_33") (pintype "bidirectional"))
      (node (ref "TVS1") (pin "2") (pinfunction "D-_2") (pintype "passive"))
      (node (ref "USB") (pin "D-") (pinfunction "2_D-") (pintype "passive"))
    )
    (net (code "61") (name "TARGET_USB_P") (class "Default")
      (node (ref "IC5") (pin "34") (pinfunction "PA25/EIC/SCOM3PAD3+/TC5_34") (pintype "bidirectional"))
      (node (ref "TVS1") (pin "1") (pinfunction "D+_1") (pintype "passive"))
      (node (ref "USB") (pin "D+") (pinfunction "3_D+") (pintype "passive"))
    )
    (net (code "62") (name "TXLED") (class "Default")
      (node (ref "IC5") (pin "39") (pinfunction "PA27/EIC_39") (pintype "bidirectional"))
      (node (ref "R18") (pin "1") (pinfunction "1_1") (pintype "passive"))
    )
    (net (code "63") (name "TXWIFI") (class "Default")
      (node (ref "IC4") (pin "21") (pinfunction "RXD_21") (pintype "input"))
      (node (ref "IC5") (pin "9") (pinfunction "PA4/EIC/REF/AIN4/SCOM0PAD0/TC0_9") (pintype "bidirectional"))
    )
    (net (code "64") (name "TX_PMS") (class "Default")
      (node (ref "CONN_DATA") (pin "13") (pinfunction "13_13") (pintype "passive"))
      (node (ref "IC5") (pin "47") (pinfunction "PB2/EIC/AIN10/SCOM5PAD0_47") (pintype "bidirectional"))
    )
    (net (code "65") (name "USB_ID") (class "Default")
      (node (ref "Q2") (pin "2") (pinfunction "G_2") (pintype "passive"))
      (node (ref "R26") (pin "1") (pinfunction "1_1") (pintype "passive"))
      (node (ref "R7") (pin "2") (pinfunction "2_2") (pintype "passive"))
      (node (ref "TVS1") (pin "3") (pinfunction "ID_3") (pintype "passive"))
      (node (ref "USB") (pin "ID") (pinfunction "4_ID") (pintype "passive"))
    )
    (net (code "66") (name "VBAT") (class "Default")
      (node (ref "BAT") (pin "2") (pinfunction "2_2") (pintype "passive"))
      (node (ref "C28") (pin "2") (pinfunction "2_2") (pintype "passive"))
      (node (ref "IC2") (pin "13") (pinfunction "VBAT_13") (pintype "bidirectional"))
      (node (ref "IC2") (pin "14") (pinfunction "VBAT_14") (pintype "bidirectional"))
    )
    (net (code "67") (name "VCC") (class "Default")
      (node (ref "C2") (pin "2") (pinfunction "2_2") (pintype "passive"))
      (node (ref "C23") (pin "2") (pinfunction "2_2") (pintype "passive"))
      (node (ref "C24") (pin "2") (pinfunction "2_2") (pintype "passive"))
      (node (ref "C25") (pin "2") (pinfunction "2_2") (pintype "passive"))
      (node (ref "C9") (pin "2") (pinfunction "2_2") (pintype "passive"))
      (node (ref "CONN_DATA") (pin "1") (pinfunction "1_1") (pintype "passive"))
      (node (ref "CONN_DATA") (pin "2") (pinfunction "2_2") (pintype "passive"))
      (node (ref "D1") (pin "-") (pinfunction "-_-") (pintype "passive"))
      (node (ref "F1") (pin "2") (pinfunction "2_2") (pintype "passive"))
      (node (ref "F2") (pin "1") (pinfunction "1_1") (pintype "passive"))
      (node (ref "IC5") (pin "17") (pinfunction "VDDIO1_17") (pintype "power_in"))
      (node (ref "IC5") (pin "36") (pinfunction "VDDIO2_36") (pintype "power_in"))
      (node (ref "IC5") (pin "44") (pinfunction "VDDIN_44") (pintype "power_in"))
      (node (ref "IC6") (pin "8") (pinfunction "VCC_8") (pintype "bidirectional"))
      (node (ref "L5") (pin "1") (pinfunction "1_1") (pintype "passive"))
      (node (ref "LED1") (pin "4") (pinfunction "A_4") (pintype "passive"))
      (node (ref "LED2") (pin "A") (pinfunction "A_A") (pintype "passive"))
      (node (ref "LED3") (pin "A") (pinfunction "A_A") (pintype "passive"))
      (node (ref "Q1") (pin "1") (pinfunction "S_1") (pintype "passive"))
      (node (ref "Q1") (pin "4") (pinfunction "S_4") (pintype "passive"))
      (node (ref "R13") (pin "2") (pinfunction "2_2") (pintype "passive"))
      (node (ref "R14") (pin "2") (pinfunction "2_2") (pintype "passive"))
      (node (ref "R16") (pin "2") (pinfunction "2_2") (pintype "passive"))
      (node (ref "R17") (pin "2") (pinfunction "2_2") (pintype "passive"))
      (node (ref "R24") (pin "2") (pinfunction "2_2") (pintype "passive"))
      (node (ref "R25") (pin "2") (pinfunction "2_2") (pintype "passive"))
      (node (ref "R26") (pin "2") (pinfunction "2_2") (pintype "passive"))
      (node (ref "R28") (pin "2") (pinfunction "2_2") (pintype "passive"))
      (node (ref "R30") (pin "2") (pinfunction "2_2") (pintype "passive"))
      (node (ref "R8") (pin "2") (pinfunction "2_2") (pintype "passive"))
      (node (ref "SD1") (pin "4") (pinfunction "VCC_4") (pintype "bidirectional"))
      (node (ref "SWD") (pin "1") (pinfunction "1_1") (pintype "passive"))
    )
    (net (code "68") (name "VCC_GROOVE") (class "Default")
      (node (ref "Q3") (pin "3") (pinfunction "D_3") (pintype "passive"))
      (node (ref "Q3") (pin "6") (pinfunction "D_6") (pintype "passive"))
      (node (ref "Q3") (pin "TP1") (pinfunction "D_TP1") (pintype "passive"))
      (node (ref "Q3") (pin "TP2") (pinfunction "D_TP2") (pintype "passive"))
      (node (ref "R22") (pin "2") (pinfunction "2_2") (pintype "passive"))
      (node (ref "R23") (pin "2") (pinfunction "2_2") (pintype "passive"))
      (node (ref "X1") (pin "3") (pinfunction "3_3") (pintype "bidirectional"))
    )
    (net (code "69") (name "VCC_WIFI") (class "Default")
      (node (ref "C1") (pin "2") (pinfunction "2_2") (pintype "passive"))
      (node (ref "IC4") (pin "1") (pinfunction "RESET_1") (pintype "input"))
      (node (ref "IC4") (pin "17") (pinfunction "GPIO2_17") (pintype "bidirectional"))
      (node (ref "IC4") (pin "8") (pinfunction "VCC_8") (pintype "power_in"))
      (node (ref "L3") (pin "1") (pinfunction "1_1") (pintype "passive"))
      (node (ref "R3") (pin "2") (pinfunction "2_2") (pintype "passive"))
    )
    (net (code "70") (name "VSYS") (class "Default")
      (node (ref "C10") (pin "2") (pinfunction "2_2") (pintype "passive"))
      (node (ref "C11") (pin "2") (pinfunction "2_2") (pintype "passive"))
      (node (ref "C15") (pin "2") (pinfunction "2_2") (pintype "passive"))
      (node (ref "C16") (pin "2") (pinfunction "2_2") (pintype "passive"))
      (node (ref "C18") (pin "2") (pinfunction "2_2") (pintype "passive"))
      (node (ref "IC1") (pin "4") (pinfunction "IN_4") (pintype "bidirectional"))
      (node (ref "IC2") (pin "15") (pinfunction "SYS_15") (pintype "bidirectional"))
      (node (ref "IC2") (pin "16") (pinfunction "SYS_16") (pintype "bidirectional"))
      (node (ref "IC3") (pin "6") (pinfunction "IN_6") (pintype "bidirectional"))
      (node (ref "L2") (pin "2") (pinfunction "2_2") (pintype "bidirectional"))
      (node (ref "L7") (pin "P$1") (pinfunction "P$1_P$1") (pintype "bidirectional"))
      (node (ref "R2") (pin "2") (pinfunction "2_2") (pintype "passive"))
      (node (ref "R5") (pin "1") (pinfunction "1_1") (pintype "passive"))
    )
    (net (code "71") (name "VUSB") (class "Default")
      (node (ref "C4") (pin "2") (pinfunction "2_2") (pintype "passive"))
      (node (ref "C5") (pin "2") (pinfunction "2_2") (pintype "passive"))
      (node (ref "C6") (pin "2") (pinfunction "2_2") (pintype "passive"))
      (node (ref "IC2") (pin "1") (pinfunction "VBUS_1") (pintype "bidirectional"))
      (node (ref "IC2") (pin "24") (pinfunction "VBUS_24") (pintype "bidirectional"))
      (node (ref "L1") (pin "2") (pinfunction "2_2") (pintype "passive"))
    )
    (net (code "72") (name "WIFI_LED") (class "Default")
      (node (ref "IC4") (pin "19") (pinfunction "GPIO5_19") (pintype "bidirectional"))
      (node (ref "R4") (pin "1") (pinfunction "1_1") (pintype "passive"))
    )
    (net (code "73") (name "unconnected-(IC2-QON-Pad12)") (class "Default")
      (node (ref "IC2") (pin "12") (pinfunction "QON_12") (pintype "bidirectional"))
    )
    (net (code "74") (name "unconnected-(IC2-STAT-Pad4)") (class "Default")
      (node (ref "IC2") (pin "4") (pinfunction "STAT_4") (pintype "bidirectional"))
    )
    (net (code "75") (name "unconnected-(IC2-{slash}PG-Pad3)") (class "Default")
      (node (ref "IC2") (pin "3") (pinfunction "/PG_3") (pintype "bidirectional"))
    )
    (net (code "76") (name "unconnected-(IC3-PG-Pad4)") (class "Default")
      (node (ref "IC3") (pin "4") (pinfunction "PG_4") (pintype "bidirectional"))
    )
    (net (code "77") (name "unconnected-(IC4-ADC-Pad2)") (class "Default")
      (node (ref "IC4") (pin "2") (pinfunction "ADC_2") (pintype "passive"))
    )
    (net (code "78") (name "unconnected-(IC4-GPIO9-Pad11)") (class "Default")
      (node (ref "IC4") (pin "11") (pinfunction "GPIO9_11") (pintype "bidirectional"))
    )
    (net (code "79") (name "unconnected-(IC4-GPIO10-Pad12)") (class "Default")
      (node (ref "IC4") (pin "12") (pinfunction "GPIO10_12") (pintype "bidirectional"))
    )
    (net (code "80") (name "unconnected-(IC4-GPIO12-Pad6)") (class "Default")
      (node (ref "IC4") (pin "6") (pinfunction "GPIO12_6") (pintype "bidirectional"))
    )
    (net (code "81") (name "unconnected-(IC4-GPIO13-Pad7)") (class "Default")
      (node (ref "IC4") (pin "7") (pinfunction "GPIO13_7") (pintype "bidirectional"))
    )
    (net (code "82") (name "unconnected-(IC4-GPIO16-Pad4)") (class "Default")
      (node (ref "IC4") (pin "4") (pinfunction "GPIO16_4") (pintype "bidirectional"))
    )
    (net (code "83") (name "unconnected-(IC4-MISO-Pad10)") (class "Default")
      (node (ref "IC4") (pin "10") (pinfunction "MISO_10") (pintype "passive"))
    )
    (net (code "84") (name "unconnected-(IC4-MOSI-Pad13)") (class "Default")
      (node (ref "IC4") (pin "13") (pinfunction "MOSI_13") (pintype "bidirectional"))
    )
    (net (code "85") (name "unconnected-(IC4-SCLK-Pad14)") (class "Default")
      (node (ref "IC4") (pin "14") (pinfunction "SCLK_14") (pintype "bidirectional"))
    )
    (net (code "86") (name "unconnected-(IC6-IO3{slash}RESET#-Pad7)") (class "Default")
      (node (ref "IC6") (pin "7") (pinfunction "IO3/RESET#_7") (pintype "bidirectional"))
    )
    (net (code "87") (name "unconnected-(IC6-WP#{slash}IO2-Pad3)") (class "Default")
      (node (ref "IC6") (pin "3") (pinfunction "WP#/IO2_3") (pintype "bidirectional"))
    )
    (net (code "88") (name "unconnected-(SD1-DAT1-Pad8)") (class "Default")
      (node (ref "SD1") (pin "8") (pinfunction "DAT1_8") (pintype "bidirectional"))
    )
    (net (code "89") (name "unconnected-(SD1-DAT2-Pad1)") (class "Default")
      (node (ref "SD1") (pin "1") (pinfunction "DAT2_1") (pintype "bidirectional"))
    )
    (net (code "90") (name "unconnected-(SWD-Pad6)") (class "Default")
      (node (ref "SWD") (pin "6") (pinfunction "6_6") (pintype "passive"))
    )
    (net (code "91") (name "unconnected-(SWD-Pad7)") (class "Default")
      (node (ref "SWD") (pin "7") (pinfunction "7_7") (pintype "passive"))
    )
    (net (code "92") (name "unconnected-(SWD-Pad8)") (class "Default")
      (node (ref "SWD") (pin "8") (pinfunction "8_8") (pintype "passive"))
    )
    (net (code "93") (name "unconnected-(TVS1-N.C.-Pad5)") (class "Default")
      (node (ref "TVS1") (pin "5") (pinfunction "N.C._5") (pintype "passive"))
    )
    (net (code "94") (name "~{INT_CCS}") (class "Default")
      (node (ref "CONN_DATA") (pin "5") (pinfunction "5_5") (pintype "passive"))
      (node (ref "IC5") (pin "13") (pinfunction "PA8/I2C/AIN16/SCOM2PAD0+/TC0_13") (pintype "bidirectional"))
    )
    (net (code "95") (name "~{WAKE_CCS}") (class "Default")
      (node (ref "CONN_DATA") (pin "7") (pinfunction "7_7") (pintype "passive"))
      (node (ref "IC5") (pin "41") (pinfunction "PA28/EIC_41") (pintype "bidirectional"))
    )
  )
)
